# R111.net
KiCad netlist of a schematic drawn in EAGLE
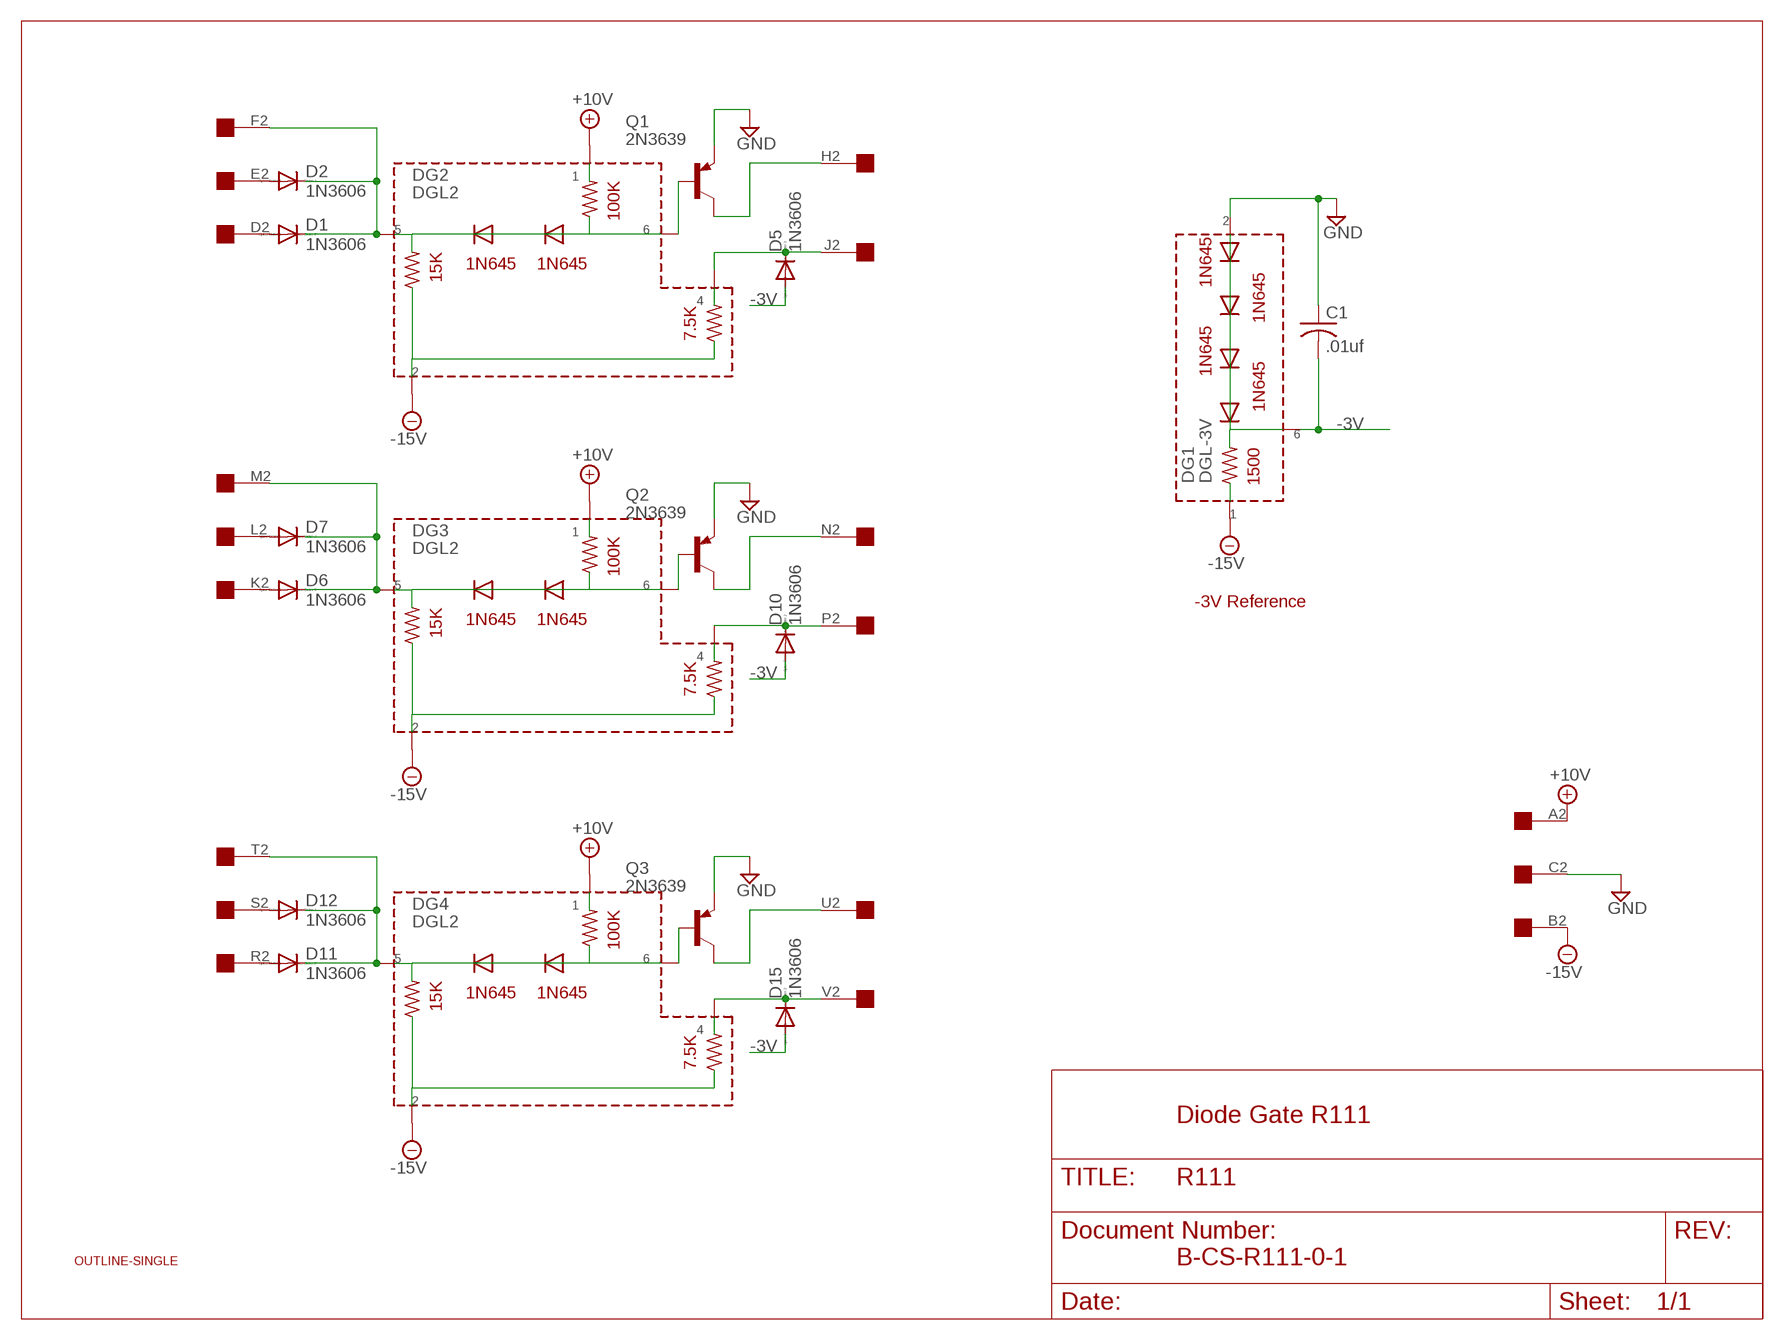
[diagram p0: schematic, sheet 1]

(export (version "E")
  (design (tool "Eeschema 10.0.6"))
  (components
    (comp (ref "C1")
      (value ".01uf")
      (footprint "eagle-import:C050-025X075")
      (libsource (lib "eagle-import") (part "C-US050-025X075"))
    )
    (comp (ref "D1")
      (value "1N3606")
      (footprint "eagle-import:DO35-10")
      (libsource (lib "eagle-import") (part "1N4148DO35-10"))
    )
    (comp (ref "D2")
      (value "1N3606")
      (footprint "eagle-import:DO35-10")
      (libsource (lib "eagle-import") (part "1N4148DO35-10"))
    )
    (comp (ref "D5")
      (value "1N3606")
      (footprint "eagle-import:DO35-10")
      (libsource (lib "eagle-import") (part "1N4148DO35-10"))
    )
    (comp (ref "D6")
      (value "1N3606")
      (footprint "eagle-import:DO35-10")
      (libsource (lib "eagle-import") (part "1N4148DO35-10"))
    )
    (comp (ref "D7")
      (value "1N3606")
      (footprint "eagle-import:DO35-10")
      (libsource (lib "eagle-import") (part "1N4148DO35-10"))
    )
    (comp (ref "D10")
      (value "1N3606")
      (footprint "eagle-import:DO35-10")
      (libsource (lib "eagle-import") (part "1N4148DO35-10"))
    )
    (comp (ref "D11")
      (value "1N3606")
      (footprint "eagle-import:DO35-10")
      (libsource (lib "eagle-import") (part "1N4148DO35-10"))
    )
    (comp (ref "D12")
      (value "1N3606")
      (footprint "eagle-import:DO35-10")
      (libsource (lib "eagle-import") (part "1N4148DO35-10"))
    )
    (comp (ref "D15")
      (value "1N3606")
      (footprint "eagle-import:DO35-10")
      (libsource (lib "eagle-import") (part "1N4148DO35-10"))
    )
    (comp (ref "DG1")
      (value "DGL-3V")
      (footprint "eagle-import:DGL2")
      (libsource (lib "eagle-import") (part "DGL-3V"))
    )
    (comp (ref "DG2")
      (value "DGL2")
      (footprint "eagle-import:DGL2")
      (libsource (lib "eagle-import") (part "DGL2"))
    )
    (comp (ref "DG3")
      (value "DGL2")
      (footprint "eagle-import:DGL2")
      (libsource (lib "eagle-import") (part "DGL2"))
    )
    (comp (ref "DG4")
      (value "DGL2")
      (footprint "eagle-import:DGL2")
      (libsource (lib "eagle-import") (part "DGL2"))
    )
    (comp (ref "Q1")
      (value "2N3639")
      (footprint "eagle-import:TO39")
      (libsource (lib "eagle-import") (part "2N3637"))
    )
    (comp (ref "Q2")
      (value "2N3639")
      (footprint "eagle-import:TO39")
      (libsource (lib "eagle-import") (part "2N3637"))
    )
    (comp (ref "Q3")
      (value "2N3639")
      (footprint "eagle-import:TO39")
      (libsource (lib "eagle-import") (part "2N3637"))
    )
    (comp (ref "U$1")
      (value "OUTLINE-SINGLE")
      (footprint "eagle-import:SINGLE")
      (libsource (lib "eagle-import") (part "OUTLINE-SINGLE"))
    )
    (comp (ref "U$2")
      (value "EDGE-1")
      (footprint "eagle-import:EDGE-CON1")
      (libsource (lib "eagle-import") (part "EDGE-1"))
    )
  )
  (nets
    (net (code "1") (name "+10V") (class "Default")
      (node (ref "DG2") (pin "P$1") (pinfunction "1_P$1") (pintype "passive"))
      (node (ref "DG3") (pin "P$1") (pinfunction "1_P$1") (pintype "passive"))
      (node (ref "DG4") (pin "P$1") (pinfunction "1_P$1") (pintype "passive"))
      (node (ref "U$2") (pin "A2") (pinfunction "1_A2") (pintype "bidirectional"))
    )
    (net (code "2") (name "-15V") (class "Default")
      (node (ref "DG1") (pin "P$1") (pinfunction "1_P$1") (pintype "passive"))
      (node (ref "DG2") (pin "P$2") (pinfunction "2_P$2") (pintype "passive"))
      (node (ref "DG3") (pin "P$2") (pinfunction "2_P$2") (pintype "passive"))
      (node (ref "DG4") (pin "P$2") (pinfunction "2_P$2") (pintype "passive"))
      (node (ref "U$2") (pin "B2") (pinfunction "1_B2") (pintype "bidirectional"))
    )
    (net (code "3") (name "/-3V") (class "Default")
      (node (ref "C1") (pin "2") (pinfunction "2_2") (pintype "passive"))
      (node (ref "D10") (pin "A") (pinfunction "A_A") (pintype "passive"))
      (node (ref "D15") (pin "A") (pinfunction "A_A") (pintype "passive"))
      (node (ref "D5") (pin "A") (pinfunction "A_A") (pintype "passive"))
      (node (ref "DG1") (pin "P$6") (pinfunction "6_P$6") (pintype "passive"))
    )
    (net (code "4") (name "GND") (class "Default")
      (node (ref "C1") (pin "1") (pinfunction "1_1") (pintype "passive"))
      (node (ref "DG1") (pin "P$2") (pinfunction "2_P$2") (pintype "passive"))
      (node (ref "Q1") (pin "1") (pinfunction "E_1") (pintype "passive"))
      (node (ref "Q2") (pin "1") (pinfunction "E_1") (pintype "passive"))
      (node (ref "Q3") (pin "1") (pinfunction "E_1") (pintype "passive"))
      (node (ref "U$2") (pin "C2") (pinfunction "1_C2") (pintype "bidirectional"))
    )
    (net (code "5") (name "Net-(DG2-4)") (class "Default")
      (node (ref "D5") (pin "C") (pinfunction "C_C") (pintype "passive"))
      (node (ref "DG2") (pin "P$4") (pinfunction "4_P$4") (pintype "passive"))
      (node (ref "U$2") (pin "J2") (pinfunction "1_J2") (pintype "bidirectional"))
    )
    (net (code "6") (name "Net-(DG2-5)") (class "Default")
      (node (ref "D1") (pin "C") (pinfunction "C_C") (pintype "passive"))
      (node (ref "D2") (pin "C") (pinfunction "C_C") (pintype "passive"))
      (node (ref "DG2") (pin "P$5") (pinfunction "5_P$5") (pintype "passive"))
      (node (ref "U$2") (pin "F2") (pinfunction "1_F2") (pintype "bidirectional"))
    )
    (net (code "7") (name "Net-(DG2-6)") (class "Default")
      (node (ref "DG2") (pin "P$6") (pinfunction "6_P$6") (pintype "passive"))
      (node (ref "Q1") (pin "2") (pinfunction "B_2") (pintype "passive"))
    )
    (net (code "8") (name "Net-(DG3-4)") (class "Default")
      (node (ref "D10") (pin "C") (pinfunction "C_C") (pintype "passive"))
      (node (ref "DG3") (pin "P$4") (pinfunction "4_P$4") (pintype "passive"))
      (node (ref "U$2") (pin "P2") (pinfunction "1_P2") (pintype "bidirectional"))
    )
    (net (code "9") (name "Net-(DG3-5)") (class "Default")
      (node (ref "D6") (pin "C") (pinfunction "C_C") (pintype "passive"))
      (node (ref "D7") (pin "C") (pinfunction "C_C") (pintype "passive"))
      (node (ref "DG3") (pin "P$5") (pinfunction "5_P$5") (pintype "passive"))
      (node (ref "U$2") (pin "M2") (pinfunction "1_M2") (pintype "bidirectional"))
    )
    (net (code "10") (name "Net-(DG3-6)") (class "Default")
      (node (ref "DG3") (pin "P$6") (pinfunction "6_P$6") (pintype "passive"))
      (node (ref "Q2") (pin "2") (pinfunction "B_2") (pintype "passive"))
    )
    (net (code "11") (name "Net-(DG4-4)") (class "Default")
      (node (ref "D15") (pin "C") (pinfunction "C_C") (pintype "passive"))
      (node (ref "DG4") (pin "P$4") (pinfunction "4_P$4") (pintype "passive"))
      (node (ref "U$2") (pin "V2") (pinfunction "1_V2") (pintype "bidirectional"))
    )
    (net (code "12") (name "Net-(DG4-5)") (class "Default")
      (node (ref "D11") (pin "C") (pinfunction "C_C") (pintype "passive"))
      (node (ref "D12") (pin "C") (pinfunction "C_C") (pintype "passive"))
      (node (ref "DG4") (pin "P$5") (pinfunction "5_P$5") (pintype "passive"))
      (node (ref "U$2") (pin "T2") (pinfunction "1_T2") (pintype "bidirectional"))
    )
    (net (code "13") (name "Net-(DG4-6)") (class "Default")
      (node (ref "DG4") (pin "P$6") (pinfunction "6_P$6") (pintype "passive"))
      (node (ref "Q3") (pin "2") (pinfunction "B_2") (pintype "passive"))
    )
    (net (code "14") (name "Net-(Q1-C)") (class "Default")
      (node (ref "Q1") (pin "3") (pinfunction "C_3") (pintype "passive"))
      (node (ref "U$2") (pin "H2") (pinfunction "1_H2") (pintype "bidirectional"))
    )
    (net (code "15") (name "Net-(Q2-C)") (class "Default")
      (node (ref "Q2") (pin "3") (pinfunction "C_3") (pintype "passive"))
      (node (ref "U$2") (pin "N2") (pinfunction "1_N2") (pintype "bidirectional"))
    )
    (net (code "16") (name "Net-(Q3-C)") (class "Default")
      (node (ref "Q3") (pin "3") (pinfunction "C_3") (pintype "passive"))
      (node (ref "U$2") (pin "U2") (pinfunction "1_U2") (pintype "bidirectional"))
    )
    (net (code "17") (name "Net-(U$2D-1)") (class "Default")
      (node (ref "D1") (pin "A") (pinfunction "A_A") (pintype "passive"))
      (node (ref "U$2") (pin "D2") (pinfunction "1_D2") (pintype "bidirectional"))
    )
    (net (code "18") (name "Net-(U$2E-1)") (class "Default")
      (node (ref "D2") (pin "A") (pinfunction "A_A") (pintype "passive"))
      (node (ref "U$2") (pin "E2") (pinfunction "1_E2") (pintype "bidirectional"))
    )
    (net (code "19") (name "Net-(U$2I-1)") (class "Default")
      (node (ref "D6") (pin "A") (pinfunction "A_A") (pintype "passive"))
      (node (ref "U$2") (pin "K2") (pinfunction "1_K2") (pintype "bidirectional"))
    )
    (net (code "20") (name "Net-(U$2J-1)") (class "Default")
      (node (ref "D7") (pin "A") (pinfunction "A_A") (pintype "passive"))
      (node (ref "U$2") (pin "L2") (pinfunction "1_L2") (pintype "bidirectional"))
    )
    (net (code "21") (name "Net-(U$2N-1)") (class "Default")
      (node (ref "D11") (pin "A") (pinfunction "A_A") (pintype "passive"))
      (node (ref "U$2") (pin "R2") (pinfunction "1_R2") (pintype "bidirectional"))
    )
    (net (code "22") (name "Net-(U$2O-1)") (class "Default")
      (node (ref "D12") (pin "A") (pinfunction "A_A") (pintype "passive"))
      (node (ref "U$2") (pin "S2") (pinfunction "1_S2") (pintype "bidirectional"))
    )
  )
)
